# Slot_periph.net
KiCad netlist of a schematic drawn in Altium Designer
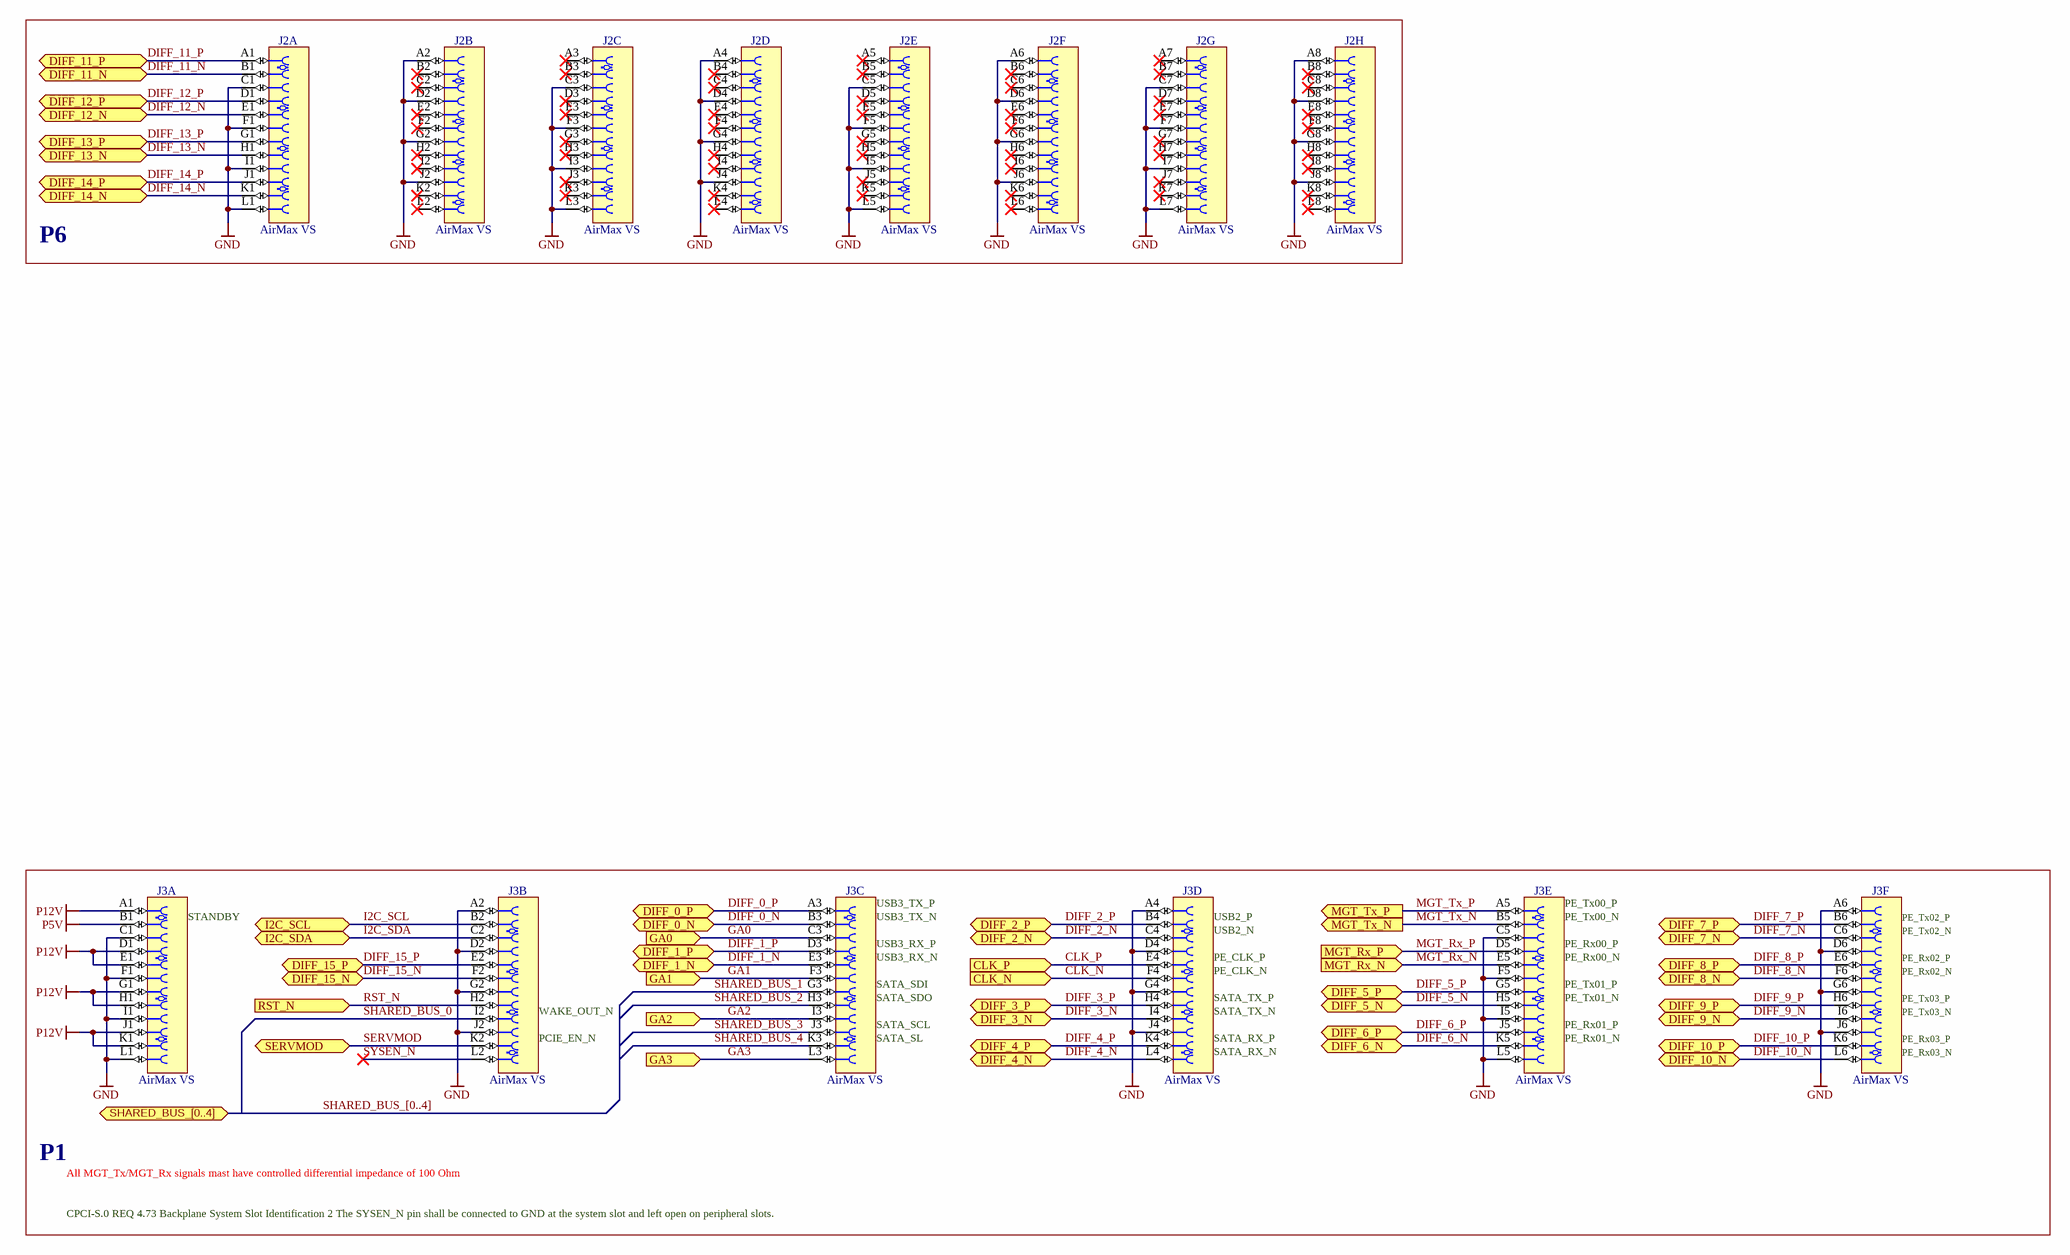
[diagram p0: Slot_periph.SchDoc]

(export (version "E")
  (design (tool "Eeschema 10.0.6"))
  (components
    (comp (ref "J2")
      (value "AirMax VS")
      (footprint "AMPHENOL_10052842-101LF")
      (description "96 Contacts Receptacle, 8 Columns, 4 Pairs per Column")
      (fields
        (field (name "PART NUMBER") "AMPHENOL_10052842-101LF")
        (field (name "MANUFACTURER") "AMPHENOL")
        (field (name "AUTHOR") "CERN DEM MR")
      )
      (libsource (lib "Connectors") (part "AMPHENOL_10052842-101LF"))
    )
    (comp (ref "J3")
      (value "AirMax VS")
      (footprint "AMPHENOL_10052829-101LF")
      (description "72 Contacts Receptacle, 6 Columns, 4 Pairs per Column")
      (fields
        (field (name "PART NUMBER") "AMPHENOL_10052829-101LF")
        (field (name "MANUFACTURER") "AMPHENOL")
        (field (name "AUTHOR") "CERN DEM MR")
      )
      (libsource (lib "Connectors") (part "AMPHENOL_10052829-101LF"))
    )
  )
  (nets
    (net (code "1") (name "/CLK_N") (class "Default")
      (node (ref "J3") (pin "F4") (pinfunction "F4_F4") (pintype "bidirectional"))
    )
    (net (code "2") (name "/CLK_P") (class "Default")
      (node (ref "J3") (pin "E4") (pinfunction "E4_E4") (pintype "bidirectional"))
    )
    (net (code "3") (name "/DIFF_0_N") (class "Default")
      (node (ref "J3") (pin "B3") (pinfunction "B3_B3") (pintype "bidirectional"))
    )
    (net (code "4") (name "/DIFF_0_P") (class "Default")
      (node (ref "J3") (pin "A3") (pinfunction "A3_A3") (pintype "bidirectional"))
    )
    (net (code "5") (name "/DIFF_1_N") (class "Default")
      (node (ref "J3") (pin "E3") (pinfunction "E3_E3") (pintype "bidirectional"))
    )
    (net (code "6") (name "/DIFF_1_P") (class "Default")
      (node (ref "J3") (pin "D3") (pinfunction "D3_D3") (pintype "bidirectional"))
    )
    (net (code "7") (name "/DIFF_2_N") (class "Default")
      (node (ref "J3") (pin "C4") (pinfunction "C4_C4") (pintype "bidirectional"))
    )
    (net (code "8") (name "/DIFF_2_P") (class "Default")
      (node (ref "J3") (pin "B4") (pinfunction "B4_B4") (pintype "bidirectional"))
    )
    (net (code "9") (name "/DIFF_3_N") (class "Default")
      (node (ref "J3") (pin "I4") (pinfunction "I4_I4") (pintype "bidirectional"))
    )
    (net (code "10") (name "/DIFF_3_P") (class "Default")
      (node (ref "J3") (pin "H4") (pinfunction "H4_H4") (pintype "bidirectional"))
    )
    (net (code "11") (name "/DIFF_4_N") (class "Default")
      (node (ref "J3") (pin "L4") (pinfunction "L4_L4") (pintype "bidirectional"))
    )
    (net (code "12") (name "/DIFF_4_P") (class "Default")
      (node (ref "J3") (pin "K4") (pinfunction "K4_K4") (pintype "bidirectional"))
    )
    (net (code "13") (name "/DIFF_5_N") (class "Default")
      (node (ref "J3") (pin "H5") (pinfunction "H5_H5") (pintype "bidirectional"))
    )
    (net (code "14") (name "/DIFF_5_P") (class "Default")
      (node (ref "J3") (pin "G5") (pinfunction "G5_G5") (pintype "bidirectional"))
    )
    (net (code "15") (name "/DIFF_6_N") (class "Default")
      (node (ref "J3") (pin "K5") (pinfunction "K5_K5") (pintype "bidirectional"))
    )
    (net (code "16") (name "/DIFF_6_P") (class "Default")
      (node (ref "J3") (pin "J5") (pinfunction "J5_J5") (pintype "bidirectional"))
    )
    (net (code "17") (name "/DIFF_7_N") (class "Default")
      (node (ref "J3") (pin "C6") (pinfunction "C6_C6") (pintype "bidirectional"))
    )
    (net (code "18") (name "/DIFF_7_P") (class "Default")
      (node (ref "J3") (pin "B6") (pinfunction "B6_B6") (pintype "bidirectional"))
    )
    (net (code "19") (name "/DIFF_8_N") (class "Default")
      (node (ref "J3") (pin "F6") (pinfunction "F6_F6") (pintype "bidirectional"))
    )
    (net (code "20") (name "/DIFF_8_P") (class "Default")
      (node (ref "J3") (pin "E6") (pinfunction "E6_E6") (pintype "bidirectional"))
    )
    (net (code "21") (name "/DIFF_9_N") (class "Default")
      (node (ref "J3") (pin "I6") (pinfunction "I6_I6") (pintype "bidirectional"))
    )
    (net (code "22") (name "/DIFF_9_P") (class "Default")
      (node (ref "J3") (pin "H6") (pinfunction "H6_H6") (pintype "bidirectional"))
    )
    (net (code "23") (name "/DIFF_10_N") (class "Default")
      (node (ref "J3") (pin "L6") (pinfunction "L6_L6") (pintype "bidirectional"))
    )
    (net (code "24") (name "/DIFF_10_P") (class "Default")
      (node (ref "J3") (pin "K6") (pinfunction "K6_K6") (pintype "bidirectional"))
    )
    (net (code "25") (name "/DIFF_11_N") (class "Default")
      (node (ref "J2") (pin "B1") (pinfunction "B1_B1") (pintype "bidirectional"))
    )
    (net (code "26") (name "/DIFF_11_P") (class "Default")
      (node (ref "J2") (pin "A1") (pinfunction "A1_A1") (pintype "bidirectional"))
    )
    (net (code "27") (name "/DIFF_12_N") (class "Default")
      (node (ref "J2") (pin "E1") (pinfunction "E1_E1") (pintype "bidirectional"))
    )
    (net (code "28") (name "/DIFF_12_P") (class "Default")
      (node (ref "J2") (pin "D1") (pinfunction "D1_D1") (pintype "bidirectional"))
    )
    (net (code "29") (name "/DIFF_13_N") (class "Default")
      (node (ref "J2") (pin "H1") (pinfunction "H1_H1") (pintype "bidirectional"))
    )
    (net (code "30") (name "/DIFF_13_P") (class "Default")
      (node (ref "J2") (pin "G1") (pinfunction "G1_G1") (pintype "bidirectional"))
    )
    (net (code "31") (name "/DIFF_14_N") (class "Default")
      (node (ref "J2") (pin "K1") (pinfunction "K1_K1") (pintype "bidirectional"))
    )
    (net (code "32") (name "/DIFF_14_P") (class "Default")
      (node (ref "J2") (pin "J1") (pinfunction "J1_J1") (pintype "bidirectional"))
    )
    (net (code "33") (name "/DIFF_15_N") (class "Default")
      (node (ref "J3") (pin "F2") (pinfunction "F2_F2") (pintype "bidirectional"))
    )
    (net (code "34") (name "/DIFF_15_P") (class "Default")
      (node (ref "J3") (pin "E2") (pinfunction "E2_E2") (pintype "bidirectional"))
    )
    (net (code "35") (name "/GA0") (class "Default")
      (node (ref "J3") (pin "C3") (pinfunction "C3_C3") (pintype "bidirectional"))
    )
    (net (code "36") (name "/GA1") (class "Default")
      (node (ref "J3") (pin "F3") (pinfunction "F3_F3") (pintype "bidirectional"))
    )
    (net (code "37") (name "/GA2") (class "Default")
      (node (ref "J3") (pin "I3") (pinfunction "I3_I3") (pintype "bidirectional"))
    )
    (net (code "38") (name "/GA3") (class "Default")
      (node (ref "J3") (pin "L3") (pinfunction "L3_L3") (pintype "bidirectional"))
    )
    (net (code "39") (name "/I2C_SCL") (class "Default")
      (node (ref "J3") (pin "B2") (pinfunction "B2_B2") (pintype "bidirectional"))
    )
    (net (code "40") (name "/I2C_SDA") (class "Default")
      (node (ref "J3") (pin "C2") (pinfunction "C2_C2") (pintype "bidirectional"))
    )
    (net (code "41") (name "/MGT_Rx_N") (class "Default")
      (node (ref "J3") (pin "E5") (pinfunction "E5_E5") (pintype "bidirectional"))
    )
    (net (code "42") (name "/MGT_Rx_P") (class "Default")
      (node (ref "J3") (pin "D5") (pinfunction "D5_D5") (pintype "bidirectional"))
    )
    (net (code "43") (name "/MGT_Tx_N") (class "Default")
      (node (ref "J3") (pin "B5") (pinfunction "B5_B5") (pintype "bidirectional"))
    )
    (net (code "44") (name "/MGT_Tx_P") (class "Default")
      (node (ref "J3") (pin "A5") (pinfunction "A5_A5") (pintype "bidirectional"))
    )
    (net (code "45") (name "/RST_N") (class "Default")
      (node (ref "J3") (pin "H2") (pinfunction "H2_H2") (pintype "bidirectional"))
    )
    (net (code "46") (name "/SERVMOD") (class "Default")
      (node (ref "J3") (pin "K2") (pinfunction "K2_K2") (pintype "bidirectional"))
    )
    (net (code "47") (name "/SHARED_BUS_0") (class "Default")
      (node (ref "J3") (pin "I2") (pinfunction "I2_I2") (pintype "bidirectional"))
    )
    (net (code "48") (name "/SHARED_BUS_1") (class "Default")
      (node (ref "J3") (pin "G3") (pinfunction "G3_G3") (pintype "bidirectional"))
    )
    (net (code "49") (name "/SHARED_BUS_2") (class "Default")
      (node (ref "J3") (pin "H3") (pinfunction "H3_H3") (pintype "bidirectional"))
    )
    (net (code "50") (name "/SHARED_BUS_3") (class "Default")
      (node (ref "J3") (pin "J3") (pinfunction "J3_J3") (pintype "bidirectional"))
    )
    (net (code "51") (name "/SHARED_BUS_4") (class "Default")
      (node (ref "J3") (pin "K3") (pinfunction "K3_K3") (pintype "bidirectional"))
    )
    (net (code "53") (name "/SYSEN_N") (class "Default")
      (node (ref "J3") (pin "L2") (pinfunction "L2_L2") (pintype "bidirectional+no_connect"))
    )
    (net (code "54") (name "GND") (class "Default")
      (node (ref "J2") (pin "A2") (pinfunction "A2_A2") (pintype "bidirectional"))
      (node (ref "J2") (pin "A4") (pinfunction "A4_A4") (pintype "bidirectional"))
      (node (ref "J2") (pin "A6") (pinfunction "A6_A6") (pintype "bidirectional"))
      (node (ref "J2") (pin "A8") (pinfunction "A8_A8") (pintype "bidirectional"))
      (node (ref "J2") (pin "C1") (pinfunction "C1_C1") (pintype "bidirectional"))
      (node (ref "J2") (pin "C3") (pinfunction "C3_C3") (pintype "bidirectional"))
      (node (ref "J2") (pin "C5") (pinfunction "C5_C5") (pintype "bidirectional"))
      (node (ref "J2") (pin "C7") (pinfunction "C7_C7") (pintype "bidirectional"))
      (node (ref "J2") (pin "D2") (pinfunction "D2_D2") (pintype "bidirectional"))
      (node (ref "J2") (pin "D4") (pinfunction "D4_D4") (pintype "bidirectional"))
      (node (ref "J2") (pin "D6") (pinfunction "D6_D6") (pintype "bidirectional"))
      (node (ref "J2") (pin "D8") (pinfunction "D8_D8") (pintype "bidirectional"))
      (node (ref "J2") (pin "F1") (pinfunction "F1_F1") (pintype "bidirectional"))
      (node (ref "J2") (pin "F3") (pinfunction "F3_F3") (pintype "bidirectional"))
      (node (ref "J2") (pin "F5") (pinfunction "F5_F5") (pintype "bidirectional"))
      (node (ref "J2") (pin "F7") (pinfunction "F7_F7") (pintype "bidirectional"))
      (node (ref "J2") (pin "G2") (pinfunction "G2_G2") (pintype "bidirectional"))
      (node (ref "J2") (pin "G4") (pinfunction "G4_G4") (pintype "bidirectional"))
      (node (ref "J2") (pin "G6") (pinfunction "G6_G6") (pintype "bidirectional"))
      (node (ref "J2") (pin "G8") (pinfunction "G8_G8") (pintype "bidirectional"))
      (node (ref "J2") (pin "I1") (pinfunction "I1_I1") (pintype "bidirectional"))
      (node (ref "J2") (pin "I3") (pinfunction "I3_I3") (pintype "bidirectional"))
      (node (ref "J2") (pin "I5") (pinfunction "I5_I5") (pintype "bidirectional"))
      (node (ref "J2") (pin "I7") (pinfunction "I7_I7") (pintype "bidirectional"))
      (node (ref "J2") (pin "J2") (pinfunction "J2_J2") (pintype "bidirectional"))
      (node (ref "J2") (pin "J4") (pinfunction "J4_J4") (pintype "bidirectional"))
      (node (ref "J2") (pin "J6") (pinfunction "J6_J6") (pintype "bidirectional"))
      (node (ref "J2") (pin "J8") (pinfunction "J8_J8") (pintype "bidirectional"))
      (node (ref "J2") (pin "L1") (pinfunction "L1_L1") (pintype "bidirectional"))
      (node (ref "J2") (pin "L3") (pinfunction "L3_L3") (pintype "bidirectional"))
      (node (ref "J2") (pin "L5") (pinfunction "L5_L5") (pintype "bidirectional"))
      (node (ref "J2") (pin "L7") (pinfunction "L7_L7") (pintype "bidirectional"))
      (node (ref "J3") (pin "A2") (pinfunction "A2_A2") (pintype "bidirectional"))
      (node (ref "J3") (pin "A4") (pinfunction "A4_A4") (pintype "bidirectional"))
      (node (ref "J3") (pin "A6") (pinfunction "A6_A6") (pintype "bidirectional"))
      (node (ref "J3") (pin "C1") (pinfunction "C1_C1") (pintype "bidirectional"))
      (node (ref "J3") (pin "C5") (pinfunction "C5_C5") (pintype "bidirectional"))
      (node (ref "J3") (pin "D2") (pinfunction "D2_D2") (pintype "bidirectional"))
      (node (ref "J3") (pin "D4") (pinfunction "D4_D4") (pintype "bidirectional"))
      (node (ref "J3") (pin "D6") (pinfunction "D6_D6") (pintype "bidirectional"))
      (node (ref "J3") (pin "F1") (pinfunction "F1_F1") (pintype "bidirectional"))
      (node (ref "J3") (pin "F5") (pinfunction "F5_F5") (pintype "bidirectional"))
      (node (ref "J3") (pin "G2") (pinfunction "G2_G2") (pintype "bidirectional"))
      (node (ref "J3") (pin "G4") (pinfunction "G4_G4") (pintype "bidirectional"))
      (node (ref "J3") (pin "G6") (pinfunction "G6_G6") (pintype "bidirectional"))
      (node (ref "J3") (pin "I1") (pinfunction "I1_I1") (pintype "bidirectional"))
      (node (ref "J3") (pin "I5") (pinfunction "I5_I5") (pintype "bidirectional"))
      (node (ref "J3") (pin "J2") (pinfunction "J2_J2") (pintype "bidirectional"))
      (node (ref "J3") (pin "J4") (pinfunction "J4_J4") (pintype "bidirectional"))
      (node (ref "J3") (pin "J6") (pinfunction "J6_J6") (pintype "bidirectional"))
      (node (ref "J3") (pin "L1") (pinfunction "L1_L1") (pintype "bidirectional"))
      (node (ref "J3") (pin "L5") (pinfunction "L5_L5") (pintype "bidirectional"))
    )
    (net (code "55") (name "P5V") (class "Default")
      (node (ref "J3") (pin "B1") (pinfunction "B1_B1") (pintype "bidirectional"))
    )
    (net (code "56") (name "P12V") (class "Default")
      (node (ref "J3") (pin "A1") (pinfunction "A1_A1") (pintype "bidirectional"))
      (node (ref "J3") (pin "D1") (pinfunction "D1_D1") (pintype "bidirectional"))
      (node (ref "J3") (pin "E1") (pinfunction "E1_E1") (pintype "bidirectional"))
      (node (ref "J3") (pin "G1") (pinfunction "G1_G1") (pintype "bidirectional"))
      (node (ref "J3") (pin "H1") (pinfunction "H1_H1") (pintype "bidirectional"))
      (node (ref "J3") (pin "J1") (pinfunction "J1_J1") (pintype "bidirectional"))
      (node (ref "J3") (pin "K1") (pinfunction "K1_K1") (pintype "bidirectional"))
    )
    (net (code "57") (name "unconnected-(J2-PadA3)") (class "Default")
      (node (ref "J2") (pin "A3") (pinfunction "A3_A3") (pintype "bidirectional+no_connect"))
    )
    (net (code "58") (name "unconnected-(J2-PadA5)") (class "Default")
      (node (ref "J2") (pin "A5") (pinfunction "A5_A5") (pintype "bidirectional+no_connect"))
    )
    (net (code "59") (name "unconnected-(J2-PadA7)") (class "Default")
      (node (ref "J2") (pin "A7") (pinfunction "A7_A7") (pintype "bidirectional+no_connect"))
    )
    (net (code "60") (name "unconnected-(J2-PadB2)") (class "Default")
      (node (ref "J2") (pin "B2") (pinfunction "B2_B2") (pintype "bidirectional+no_connect"))
    )
    (net (code "61") (name "unconnected-(J2-PadB3)") (class "Default")
      (node (ref "J2") (pin "B3") (pinfunction "B3_B3") (pintype "bidirectional+no_connect"))
    )
    (net (code "62") (name "unconnected-(J2-PadB4)") (class "Default")
      (node (ref "J2") (pin "B4") (pinfunction "B4_B4") (pintype "bidirectional+no_connect"))
    )
    (net (code "63") (name "unconnected-(J2-PadB5)") (class "Default")
      (node (ref "J2") (pin "B5") (pinfunction "B5_B5") (pintype "bidirectional+no_connect"))
    )
    (net (code "64") (name "unconnected-(J2-PadB6)") (class "Default")
      (node (ref "J2") (pin "B6") (pinfunction "B6_B6") (pintype "bidirectional+no_connect"))
    )
    (net (code "65") (name "unconnected-(J2-PadB7)") (class "Default")
      (node (ref "J2") (pin "B7") (pinfunction "B7_B7") (pintype "bidirectional+no_connect"))
    )
    (net (code "66") (name "unconnected-(J2-PadB8)") (class "Default")
      (node (ref "J2") (pin "B8") (pinfunction "B8_B8") (pintype "bidirectional+no_connect"))
    )
    (net (code "67") (name "unconnected-(J2-PadC2)") (class "Default")
      (node (ref "J2") (pin "C2") (pinfunction "C2_C2") (pintype "bidirectional+no_connect"))
    )
    (net (code "68") (name "unconnected-(J2-PadC4)") (class "Default")
      (node (ref "J2") (pin "C4") (pinfunction "C4_C4") (pintype "bidirectional+no_connect"))
    )
    (net (code "69") (name "unconnected-(J2-PadC6)") (class "Default")
      (node (ref "J2") (pin "C6") (pinfunction "C6_C6") (pintype "bidirectional+no_connect"))
    )
    (net (code "70") (name "unconnected-(J2-PadC8)") (class "Default")
      (node (ref "J2") (pin "C8") (pinfunction "C8_C8") (pintype "bidirectional+no_connect"))
    )
    (net (code "71") (name "unconnected-(J2-PadD3)") (class "Default")
      (node (ref "J2") (pin "D3") (pinfunction "D3_D3") (pintype "bidirectional+no_connect"))
    )
    (net (code "72") (name "unconnected-(J2-PadD5)") (class "Default")
      (node (ref "J2") (pin "D5") (pinfunction "D5_D5") (pintype "bidirectional+no_connect"))
    )
    (net (code "73") (name "unconnected-(J2-PadD7)") (class "Default")
      (node (ref "J2") (pin "D7") (pinfunction "D7_D7") (pintype "bidirectional+no_connect"))
    )
    (net (code "74") (name "unconnected-(J2-PadE2)") (class "Default")
      (node (ref "J2") (pin "E2") (pinfunction "E2_E2") (pintype "bidirectional+no_connect"))
    )
    (net (code "75") (name "unconnected-(J2-PadE3)") (class "Default")
      (node (ref "J2") (pin "E3") (pinfunction "E3_E3") (pintype "bidirectional+no_connect"))
    )
    (net (code "76") (name "unconnected-(J2-PadE4)") (class "Default")
      (node (ref "J2") (pin "E4") (pinfunction "E4_E4") (pintype "bidirectional+no_connect"))
    )
    (net (code "77") (name "unconnected-(J2-PadE5)") (class "Default")
      (node (ref "J2") (pin "E5") (pinfunction "E5_E5") (pintype "bidirectional+no_connect"))
    )
    (net (code "78") (name "unconnected-(J2-PadE6)") (class "Default")
      (node (ref "J2") (pin "E6") (pinfunction "E6_E6") (pintype "bidirectional+no_connect"))
    )
    (net (code "79") (name "unconnected-(J2-PadE7)") (class "Default")
      (node (ref "J2") (pin "E7") (pinfunction "E7_E7") (pintype "bidirectional+no_connect"))
    )
    (net (code "80") (name "unconnected-(J2-PadE8)") (class "Default")
      (node (ref "J2") (pin "E8") (pinfunction "E8_E8") (pintype "bidirectional+no_connect"))
    )
    (net (code "81") (name "unconnected-(J2-PadF2)") (class "Default")
      (node (ref "J2") (pin "F2") (pinfunction "F2_F2") (pintype "bidirectional+no_connect"))
    )
    (net (code "82") (name "unconnected-(J2-PadF4)") (class "Default")
      (node (ref "J2") (pin "F4") (pinfunction "F4_F4") (pintype "bidirectional+no_connect"))
    )
    (net (code "83") (name "unconnected-(J2-PadF6)") (class "Default")
      (node (ref "J2") (pin "F6") (pinfunction "F6_F6") (pintype "bidirectional+no_connect"))
    )
    (net (code "84") (name "unconnected-(J2-PadF8)") (class "Default")
      (node (ref "J2") (pin "F8") (pinfunction "F8_F8") (pintype "bidirectional+no_connect"))
    )
    (net (code "85") (name "unconnected-(J2-PadG3)") (class "Default")
      (node (ref "J2") (pin "G3") (pinfunction "G3_G3") (pintype "bidirectional+no_connect"))
    )
    (net (code "86") (name "unconnected-(J2-PadG5)") (class "Default")
      (node (ref "J2") (pin "G5") (pinfunction "G5_G5") (pintype "bidirectional+no_connect"))
    )
    (net (code "87") (name "unconnected-(J2-PadG7)") (class "Default")
      (node (ref "J2") (pin "G7") (pinfunction "G7_G7") (pintype "bidirectional+no_connect"))
    )
    (net (code "88") (name "unconnected-(J2-PadH2)") (class "Default")
      (node (ref "J2") (pin "H2") (pinfunction "H2_H2") (pintype "bidirectional+no_connect"))
    )
    (net (code "89") (name "unconnected-(J2-PadH3)") (class "Default")
      (node (ref "J2") (pin "H3") (pinfunction "H3_H3") (pintype "bidirectional+no_connect"))
    )
    (net (code "90") (name "unconnected-(J2-PadH4)") (class "Default")
      (node (ref "J2") (pin "H4") (pinfunction "H4_H4") (pintype "bidirectional+no_connect"))
    )
    (net (code "91") (name "unconnected-(J2-PadH5)") (class "Default")
      (node (ref "J2") (pin "H5") (pinfunction "H5_H5") (pintype "bidirectional+no_connect"))
    )
    (net (code "92") (name "unconnected-(J2-PadH6)") (class "Default")
      (node (ref "J2") (pin "H6") (pinfunction "H6_H6") (pintype "bidirectional+no_connect"))
    )
    (net (code "93") (name "unconnected-(J2-PadH7)") (class "Default")
      (node (ref "J2") (pin "H7") (pinfunction "H7_H7") (pintype "bidirectional+no_connect"))
    )
    (net (code "94") (name "unconnected-(J2-PadH8)") (class "Default")
      (node (ref "J2") (pin "H8") (pinfunction "H8_H8") (pintype "bidirectional+no_connect"))
    )
    (net (code "95") (name "unconnected-(J2-PadI2)") (class "Default")
      (node (ref "J2") (pin "I2") (pinfunction "I2_I2") (pintype "bidirectional+no_connect"))
    )
    (net (code "96") (name "unconnected-(J2-PadI4)") (class "Default")
      (node (ref "J2") (pin "I4") (pinfunction "I4_I4") (pintype "bidirectional+no_connect"))
    )
    (net (code "97") (name "unconnected-(J2-PadI6)") (class "Default")
      (node (ref "J2") (pin "I6") (pinfunction "I6_I6") (pintype "bidirectional+no_connect"))
    )
    (net (code "98") (name "unconnected-(J2-PadI8)") (class "Default")
      (node (ref "J2") (pin "I8") (pinfunction "I8_I8") (pintype "bidirectional+no_connect"))
    )
    (net (code "99") (name "unconnected-(J2-PadJ3)") (class "Default")
      (node (ref "J2") (pin "J3") (pinfunction "J3_J3") (pintype "bidirectional+no_connect"))
    )
    (net (code "100") (name "unconnected-(J2-PadJ5)") (class "Default")
      (node (ref "J2") (pin "J5") (pinfunction "J5_J5") (pintype "bidirectional+no_connect"))
    )
    (net (code "101") (name "unconnected-(J2-PadJ7)") (class "Default")
      (node (ref "J2") (pin "J7") (pinfunction "J7_J7") (pintype "bidirectional+no_connect"))
    )
    (net (code "102") (name "unconnected-(J2-PadK2)") (class "Default")
      (node (ref "J2") (pin "K2") (pinfunction "K2_K2") (pintype "bidirectional+no_connect"))
    )
    (net (code "103") (name "unconnected-(J2-PadK3)") (class "Default")
      (node (ref "J2") (pin "K3") (pinfunction "K3_K3") (pintype "bidirectional+no_connect"))
    )
    (net (code "104") (name "unconnected-(J2-PadK4)") (class "Default")
      (node (ref "J2") (pin "K4") (pinfunction "K4_K4") (pintype "bidirectional+no_connect"))
    )
    (net (code "105") (name "unconnected-(J2-PadK5)") (class "Default")
      (node (ref "J2") (pin "K5") (pinfunction "K5_K5") (pintype "bidirectional+no_connect"))
    )
    (net (code "106") (name "unconnected-(J2-PadK6)") (class "Default")
      (node (ref "J2") (pin "K6") (pinfunction "K6_K6") (pintype "bidirectional+no_connect"))
    )
    (net (code "107") (name "unconnected-(J2-PadK7)") (class "Default")
      (node (ref "J2") (pin "K7") (pinfunction "K7_K7") (pintype "bidirectional+no_connect"))
    )
    (net (code "108") (name "unconnected-(J2-PadK8)") (class "Default")
      (node (ref "J2") (pin "K8") (pinfunction "K8_K8") (pintype "bidirectional+no_connect"))
    )
    (net (code "109") (name "unconnected-(J2-PadL2)") (class "Default")
      (node (ref "J2") (pin "L2") (pinfunction "L2_L2") (pintype "bidirectional+no_connect"))
    )
    (net (code "110") (name "unconnected-(J2-PadL4)") (class "Default")
      (node (ref "J2") (pin "L4") (pinfunction "L4_L4") (pintype "bidirectional+no_connect"))
    )
    (net (code "111") (name "unconnected-(J2-PadL6)") (class "Default")
      (node (ref "J2") (pin "L6") (pinfunction "L6_L6") (pintype "bidirectional+no_connect"))
    )
    (net (code "112") (name "unconnected-(J2-PadL8)") (class "Default")
      (node (ref "J2") (pin "L8") (pinfunction "L8_L8") (pintype "bidirectional+no_connect"))
    )
  )
)
